# Input.net
KiCad netlist of a schematic drawn in Altium Designer
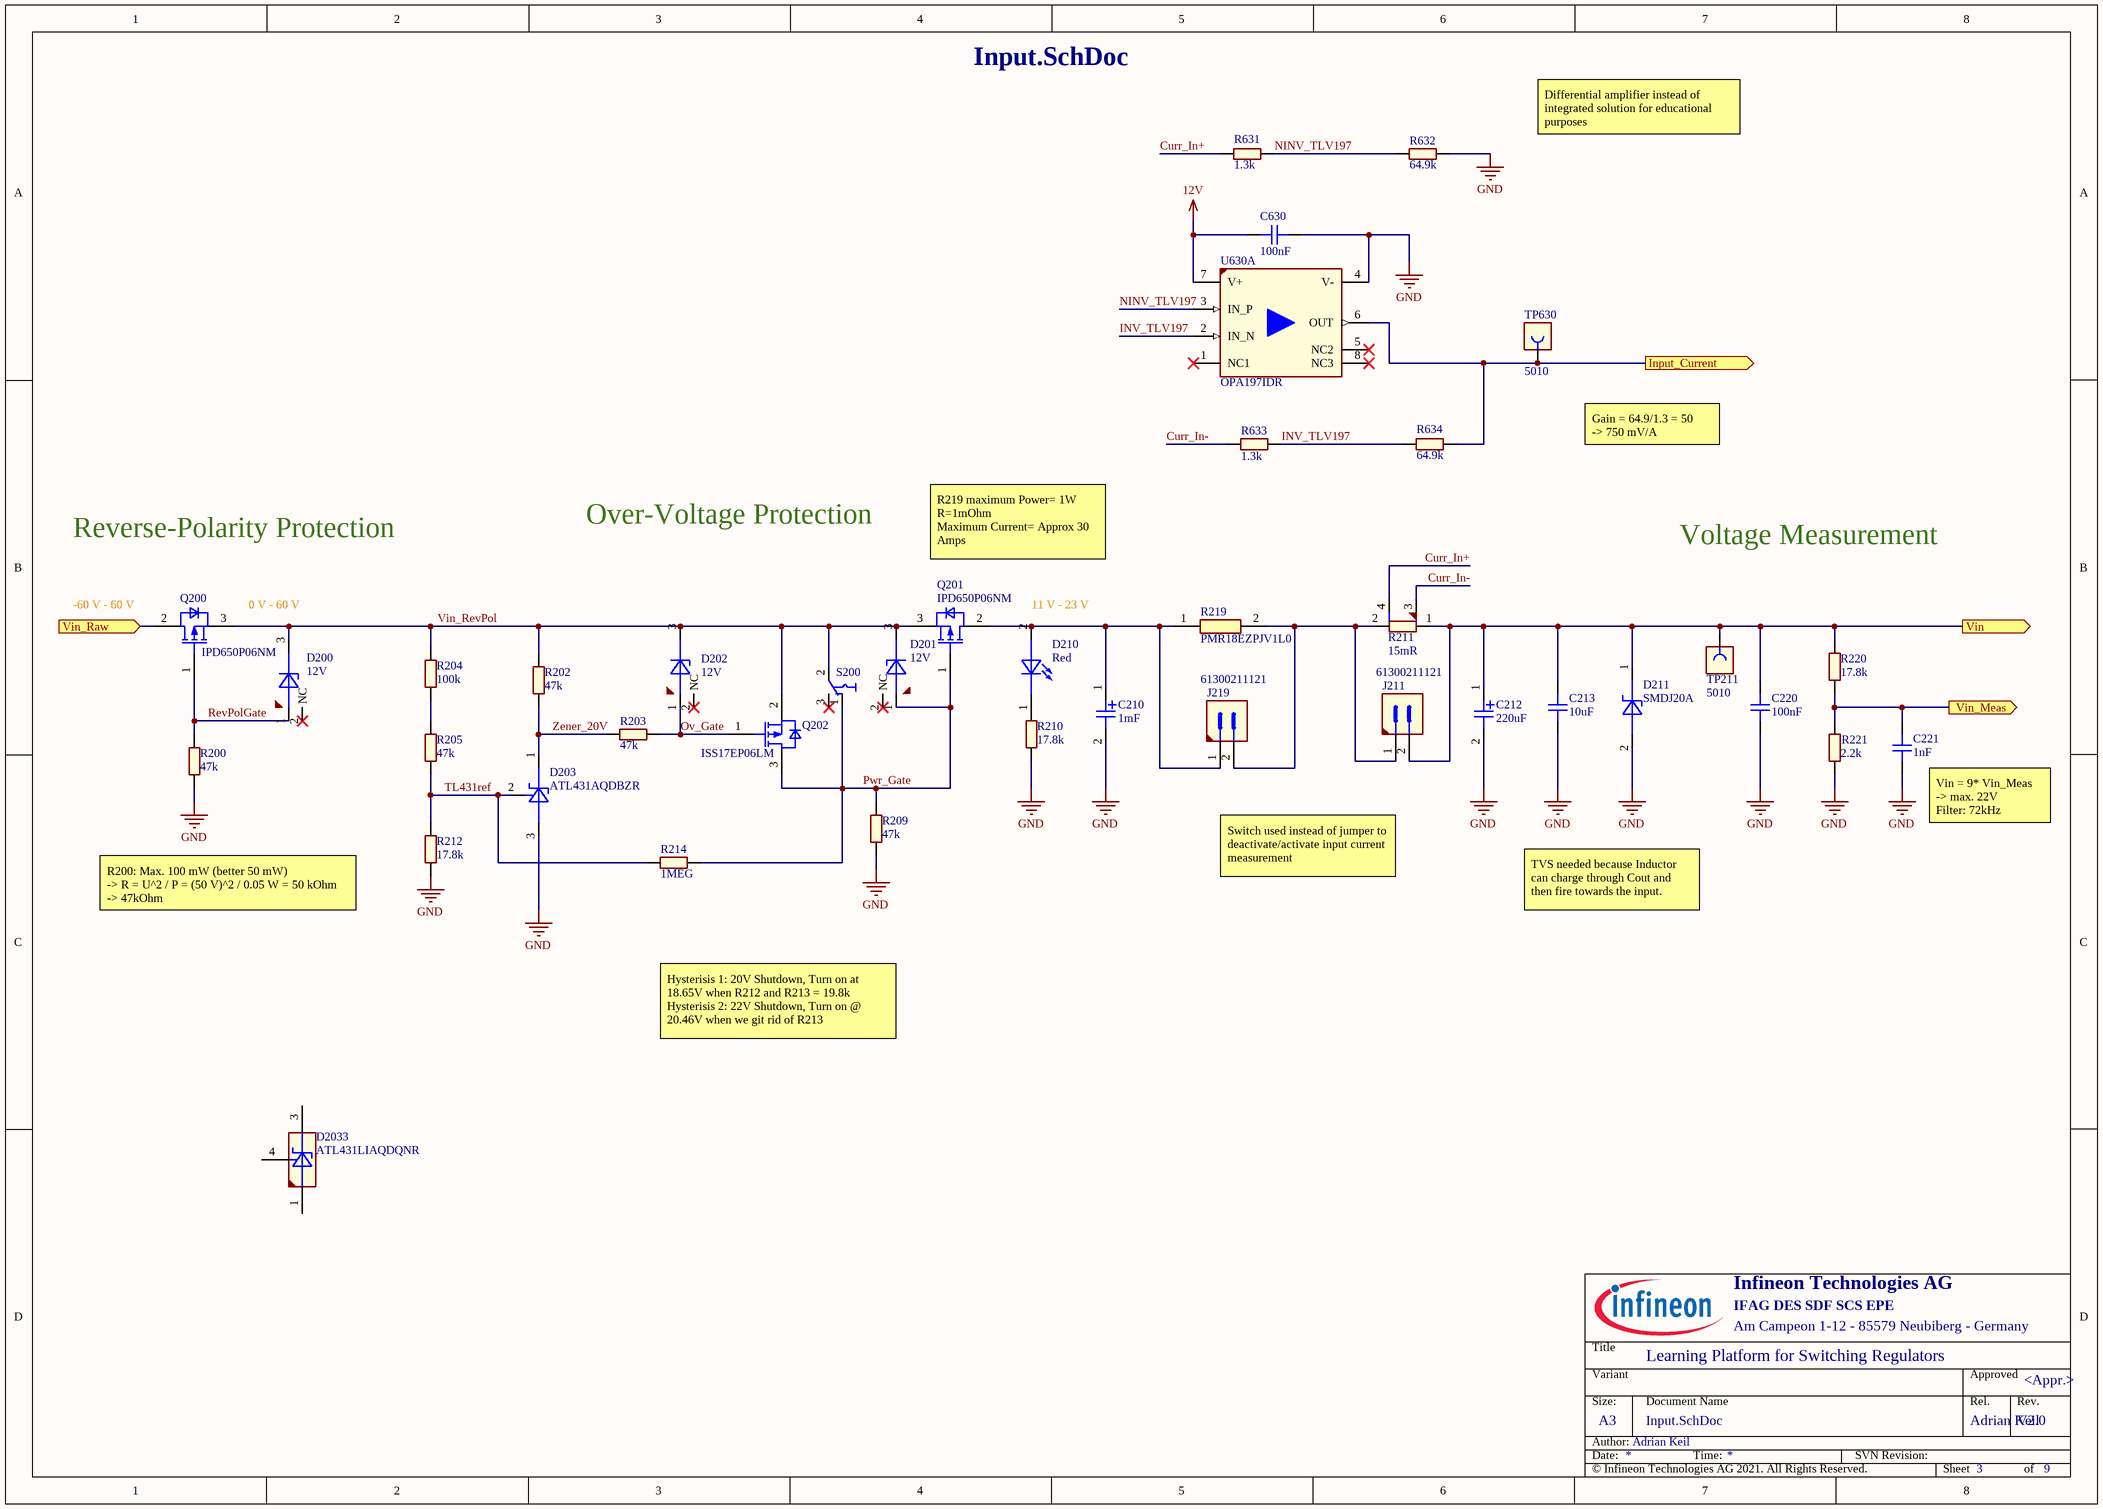
[diagram p0: Input.SchDoc]

(export (version "E")
  (design (tool "Eeschema 10.0.6"))
  (components
    (comp (ref "C210")
      (value "1mF")
      (footprint "CAPPRD500W60D1300H2700B")
      (fields (field (name "MANUFACTURER") "Kemet"))
      (libsource (lib "PCBLibraryData") (part "CAP-SGL-POL-02P_00000002"))
    )
    (comp (ref "C212")
      (value "220uF")
      (footprint "CAPAE1030X1050N-3")
      (fields (field (name "MANUFACTURER") "Nippon Chemi-Con"))
      (libsource (lib "PCBLibraryData") (part "CAP-SGL-POL-02P_00000002"))
    )
    (comp (ref "C213")
      (value "10uF")
      (footprint "CAPC3216X190N-1")
      (description "CAP / CERA / 10uF / 50V / 20% / X5R (EIA) / -55°C to 85°C / 1206 (3216) / SMD / -")
      (fields (field (name "MANUFACTURER") "Taiyo Yuden"))
      (libsource (lib "PCBLibraryData") (part "CAP-SGL-STD-02P_00000001"))
    )
    (comp (ref "C220")
      (value "100nF")
      (footprint "CAPC3216X125N-0")
      (description "CAP / CERA / 100nF / 50V / 10% / X7R (EIA) / -55°C to 125°C / 1206(3216) / SMD / -")
      (fields (field (name "LEGACY PARTNUMBER") "CAP01005660") (field (name "MANUFACTURER") "MuRata"))
      (libsource (lib "PCBLibraryData") (part "CAP-SGL-STD-02P_00000001"))
    )
    (comp (ref "C221")
      (value "1nF")
      (footprint "CAPC3216X95N")
      (description "CAP / CERA / 1nF / 50V / 10% / X7R (EIA) / -55°C to 125°C / 1206(3216) / SMD / -")
      (fields (field (name "LEGACY PARTNUMBER") "CAP01005183") (field (name "MANUFACTURER") "MuRata"))
      (libsource (lib "PCBLibraryData") (part "CAP-SGL-STD-02P_00000001"))
    )
    (comp (ref "C630")
      (value "100nF")
      (footprint "CAPC3216X125N-0")
      (description "CAP / CERA / 100nF / 50V / 10% / X7R (EIA) / -55°C to 125°C / 1206(3216) / SMD / -")
      (fields (field (name "LEGACY PARTNUMBER") "CAP01005660") (field (name "MANUFACTURER") "MuRata"))
      (libsource (lib "PCBLibraryData") (part "CAP-SGL-STD-02P_00000001"))
    )
    (comp (ref "D200")
      (value "12V")
      (footprint "SOT95P230X110-3N")
      (description "Voltage regulator diodes")
      (fields (field (name "MANUFACTURER") "Nexperia"))
      (libsource (lib "PCBLibraryData") (part "d_zener_a1c3_3p"))
    )
    (comp (ref "D201")
      (value "12V")
      (footprint "SOT95P230X110-3N")
      (description "Voltage regulator diodes")
      (fields (field (name "MANUFACTURER") "Nexperia"))
      (libsource (lib "PCBLibraryData") (part "d_zener_a1c3_3p"))
    )
    (comp (ref "D202")
      (value "12V")
      (footprint "SOT95P230X110-3N")
      (description "Voltage regulator diodes")
      (fields (field (name "MANUFACTURER") "Nexperia"))
      (libsource (lib "PCBLibraryData") (part "d_zener_a1c3_3p"))
    )
    (comp (ref "D203")
      (value "ATL431AQDBZR")
      (footprint "SOT95P237X112-3N-1")
      (description "ATL431 Adjustable Precision Shunt Regulator")
      (fields (field (name "MANUFACTURER") "Texas Instruments"))
      (libsource (lib "PCBLibraryData") (part "d_tvs_c1a3_3p"))
    )
    (comp (ref "D210")
      (value "Red")
      (footprint "LEDSC160X80X80-2N-1")
      (description "WL-SMCW SMT Mono-color Chip LED Waterclear, Red,630nm")
      (fields (field (name "MANUFACTURER") "Wurth Elektronik"))
      (libsource (lib "PCBLibraryData") (part "d_led_a"))
    )
    (comp (ref "D211")
      (value "SMDJ20A")
      (footprint "DIOM7959X262N")
      (description "TVS Diode, Low Profile Package, Built in Strain Relief, Glass Passivated Chip Junction")
      (fields (field (name "MANUFACTURER") "Littelfuse"))
      (libsource (lib "PCBLibraryData") (part "d_tvs_a"))
    )
    (comp (ref "D2033")
      (value "ATL431LIAQDQNR")
      (footprint "TI-SMD-X2SON-V")
      (description "High Bandwidth Low-Iq Programmable Shunt Regulator")
      (fields (field (name "MANUFACTURER") "Texas Instruments"))
      (libsource (lib "PCBLibraryData") (part "ATL431LIXXDQNX"))
    )
    (comp (ref "J211")
      (value "61300211121")
      (footprint "CON-M-THT-61300211121")
      (description "Header, 2.54mm Pitch, 2 pin, Vertical, Single Row")
      (fields
        (field (name "LEGACY PARTNUMBER") "CON01500943")
        (field (name "MANUFACTURER") "Wurth Elektronik")
      )
      (libsource (lib "PCBLibraryData") (part "Header 2"))
    )
    (comp (ref "J219")
      (value "61300211121")
      (footprint "CON-M-THT-61300211121")
      (description "Header, 2.54mm Pitch, 2 pin, Vertical, Single Row")
      (fields
        (field (name "LEGACY PARTNUMBER") "CON01500943")
        (field (name "MANUFACTURER") "Wurth Elektronik")
      )
      (libsource (lib "PCBLibraryData") (part "Header 2"))
    )
    (comp (ref "Q200")
      (value "IPD650P06NM")
      (footprint "TO228P998X250-3N-V2")
      (description "OptiMOS Power Transistor, -60 V")
      (fields (field (name "MANUFACTURER") "Infineon Technologies"))
      (libsource (lib "PCBLibraryData") (part "igfet_p_ch_enh_dio_1g2d3s_3p"))
    )
    (comp (ref "Q201")
      (value "IPD650P06NM")
      (footprint "TO228P998X250-3N-V2")
      (description "OptiMOS Power Transistor, -60 V")
      (fields (field (name "MANUFACTURER") "Infineon Technologies"))
      (libsource (lib "PCBLibraryData") (part "igfet_p_ch_enh_dio_1g2d3s_3p"))
    )
    (comp (ref "Q202")
      (value "ISS17EP06LM")
      (footprint "SOT95P240X110-3N-1-V")
      (description "OptiMOSTM Small Signal Transistor, -60 V")
      (fields (field (name "MANUFACTURER") "Infineon Technologies"))
      (libsource (lib "PCBLibraryData") (part "igfet_p_ch_enh_dio_1g2s3d_3p"))
    )
    (comp (ref "R200")
      (value "47k")
      (footprint "RESC3216X60N")
      (description "RES / STD / 47k / 250mW / 1% / 100ppm/K / -55°C to 155°C / 1206(3216) / SMD / -")
      (fields (field (name "LEGACY PARTNUMBER") "RES01802933") (field (name "MANUFACTURER") "Vishay"))
      (libsource (lib "PCBLibraryData") (part "RES-SGL-STD-02P_00000006"))
    )
    (comp (ref "R202")
      (value "47k")
      (footprint "RESC3216X60N")
      (description "RES / STD / 47k / 250mW / 1% / 100ppm/K / -55°C to 155°C / 1206(3216) / SMD / -")
      (fields (field (name "LEGACY PARTNUMBER") "RES01802933") (field (name "MANUFACTURER") "Vishay"))
      (libsource (lib "PCBLibraryData") (part "RES-SGL-STD-02P_00000006"))
    )
    (comp (ref "R203")
      (value "47k")
      (footprint "RESC3216X60N")
      (description "RES / STD / 47k / 250mW / 1% / 100ppm/K / -55°C to 155°C / 1206(3216) / SMD / -")
      (fields (field (name "LEGACY PARTNUMBER") "RES01802933") (field (name "MANUFACTURER") "Vishay"))
      (libsource (lib "") (part "RES-SGL-STD-02P_00000006_2"))
    )
    (comp (ref "R204")
      (value "100k")
      (footprint "RESC3216X60N")
      (description "RES / STD / 100k / 250mW / 1% / 100ppm/K / -55°C to 155°C / 1206(3216) / SMD / -")
      (fields (field (name "LEGACY PARTNUMBER") "RES01802971") (field (name "MANUFACTURER") "Vishay"))
      (libsource (lib "") (part "RES-SGL-STD-02P_00000006_3"))
    )
    (comp (ref "R205")
      (value "47k")
      (footprint "RESC3216X60N")
      (description "RES / STD / 47k / 250mW / 1% / 100ppm/K / -55°C to 155°C / 1206(3216) / SMD / -")
      (fields (field (name "LEGACY PARTNUMBER") "RES01802933") (field (name "MANUFACTURER") "Vishay"))
      (libsource (lib "PCBLibraryData") (part "RES-SGL-STD-02P_00000006"))
    )
    (comp (ref "R209")
      (value "47k")
      (footprint "RESC3216X60N")
      (description "RES / STD / 47k / 250mW / 1% / 100ppm/K / -55°C to 155°C / 1206(3216) / SMD / -")
      (fields (field (name "LEGACY PARTNUMBER") "RES01802933") (field (name "MANUFACTURER") "Vishay"))
      (libsource (lib "PCBLibraryData") (part "RES-SGL-STD-02P_00000006"))
    )
    (comp (ref "R210")
      (value "17.8k")
      (footprint "RESC3216X60N")
      (description "RES / STD / 17.8k / 250mW / 1% / 100ppm/K / -55°C to 155°C / 1206(3216) / SMD / -")
      (fields (field (name "LEGACY PARTNUMBER") "RES01802883") (field (name "MANUFACTURER") "Vishay"))
      (libsource (lib "") (part "RES-SGL-STD-02P_00000006_3"))
    )
    (comp (ref "R211")
      (value "15mR")
      (footprint "RES-SMD-L4T12")
      (description "RES / STD / 15mR / 500mW / 1% / 75ppm/K / -55°C to 155°C / 1206 (3216) / SMD / -")
      (fields (field (name "MANUFACTURER") "Ohmite"))
      (libsource (lib "PCBLibraryData") (part "RES-SHT-STD-04P_00097BE5"))
    )
    (comp (ref "R212")
      (value "17.8k")
      (footprint "RESC3216X60N")
      (description "RES / STD / 17.8k / 250mW / 1% / 100ppm/K / -55°C to 155°C / 1206(3216) / SMD / -")
      (fields (field (name "LEGACY PARTNUMBER") "RES01802883") (field (name "MANUFACTURER") "Vishay"))
      (libsource (lib "") (part "RES-SGL-STD-02P_00000006_3"))
    )
    (comp (ref "R214")
      (value "1MEG")
      (footprint "RESC3216X60N")
      (description "RES / STD / 1MEG / 250mW / 1% / 100ppm/K / -55°C to 155°C / 1206(3216) / SMD / -")
      (fields (field (name "LEGACY PARTNUMBER") "RES01803085") (field (name "MANUFACTURER") "Vishay"))
      (libsource (lib "") (part "RES-SGL-STD-02P_00000006_1"))
    )
    (comp (ref "R219")
      (value "PMR18EZPJV1L0")
      (footprint "SamacSys:RESC3216X59N")
      (description "Resistor")
      (fields (field (name "MOUSER PART NUMBER") "755-PMR18EZPJV1L0"))
      (libsource (lib "*") (part "PMR18EZPJV1L0"))
    )
    (comp (ref "R220")
      (value "17.8k")
      (footprint "RESC3216X60N")
      (description "RES / STD / 17.8k / 250mW / 1% / 100ppm/K / -55°C to 155°C / 1206(3216) / SMD / -")
      (fields (field (name "LEGACY PARTNUMBER") "RES01802883") (field (name "MANUFACTURER") "Vishay"))
      (libsource (lib "") (part "RES-SGL-STD-02P_00000006_3"))
    )
    (comp (ref "R221")
      (value "2.2k")
      (footprint "RESC3216X60N")
      (description "RES / STD / 2.2k / 250mW / 1% / 100ppm/K / -55°C to 155°C / 1206(3216) / SMD / -")
      (fields (field (name "LEGACY PARTNUMBER") "RES01802779") (field (name "MANUFACTURER") "Vishay"))
      (libsource (lib "") (part "RES-SGL-STD-02P_00000006_3"))
    )
    (comp (ref "R631")
      (value "1.3k")
      (footprint "RESC3216X60N")
      (description "RES / STD / 1.3k / 250mW / 1% / 100ppm/K / -55°C to 155°C / 1206(3216) / SMD / -")
      (fields (field (name "LEGACY PARTNUMBER") "RES01802755") (field (name "MANUFACTURER") "Vishay"))
      (libsource (lib "") (part "RES-SGL-STD-02P_00000006_1"))
    )
    (comp (ref "R632")
      (value "64.9k")
      (footprint "RESC3216X60N")
      (description "RES / STD / 64.9k / 250mW / 1% / 100ppm/K / -55°C to 155°C / 1206(3216) / SMD / -")
      (fields (field (name "LEGACY PARTNUMBER") "RES01802950") (field (name "MANUFACTURER") "Vishay"))
      (libsource (lib "") (part "RES-SGL-STD-02P_00000006_1"))
    )
    (comp (ref "R633")
      (value "1.3k")
      (footprint "RESC3216X60N")
      (description "RES / STD / 1.3k / 250mW / 1% / 100ppm/K / -55°C to 155°C / 1206(3216) / SMD / -")
      (fields (field (name "LEGACY PARTNUMBER") "RES01802755") (field (name "MANUFACTURER") "Vishay"))
      (libsource (lib "") (part "RES-SGL-STD-02P_00000006_1"))
    )
    (comp (ref "R634")
      (value "64.9k")
      (footprint "RESC3216X60N")
      (description "RES / STD / 64.9k / 250mW / 1% / 100ppm/K / -55°C to 155°C / 1206(3216) / SMD / -")
      (fields (field (name "LEGACY PARTNUMBER") "RES01802950") (field (name "MANUFACTURER") "Vishay"))
      (libsource (lib "") (part "RES-SGL-STD-02P_00000006_1"))
    )
    (comp (ref "S200")
      (value "CL-SB-12A-01T")
      (footprint "SW-SMD-CL-SB-12A-01T")
      (description "Slid Switch, 12V, 200mA")
      (fields (field (name "MANUFACTURER") "NIDEC COPAL ELECTRONICS, Inc."))
      (libsource (lib "PCBLibraryData") (part "sw_co213_3p"))
    )
    (comp (ref "TP211")
      (value "5010")
      (footprint "CON-THT-TP-5010")
      (description "PC Test Point-Multipurpose THT, Red")
      (fields
        (field (name "LEGACY PARTNUMBER") "CON01500529")
        (field (name "MANUFACTURER") "Keystone Electronics Corp.")
      )
      (libsource (lib "") (part "connector_1_f_1"))
    )
    (comp (ref "TP630")
      (value "5010")
      (footprint "CON-THT-TP-5010")
      (description "PC Test Point-Multipurpose THT, Red")
      (fields
        (field (name "LEGACY PARTNUMBER") "CON01500529")
        (field (name "MANUFACTURER") "Keystone Electronics Corp.")
      )
      (libsource (lib "PCBLibraryData") (part "connector_1_f"))
    )
    (comp (ref "U630")
      (value "OPA197IDR")
      (footprint "SOIC127P600X175-8N-23")
      (fields (field (name "MANUFACTURER") "Texas Instruments"))
      (libsource (lib "PCBLibraryData") (part "OPA140AID"))
    )
  )
  (nets
    (net (code "1") (name "/Curr_In+") (class "Default")
      (node (ref "R211") (pin "4") (pinfunction "I2_4") (pintype "passive"))
      (node (ref "R631") (pin "1") (pinfunction "1_1") (pintype "passive"))
    )
    (net (code "2") (name "/Curr_In-") (class "Default")
      (node (ref "R211") (pin "3") (pinfunction "I1_3") (pintype "passive"))
      (node (ref "R633") (pin "1") (pinfunction "1_1") (pintype "passive"))
    )
    (net (code "3") (name "/INV_TLV197") (class "Default")
      (node (ref "R633") (pin "2") (pinfunction "2_2") (pintype "passive"))
      (node (ref "R634") (pin "1") (pinfunction "1_1") (pintype "passive"))
      (node (ref "U630") (pin "2") (pinfunction "IN_N_2") (pintype "input"))
    )
    (net (code "4") (name "/Input_Current") (class "Default")
      (node (ref "R634") (pin "2") (pinfunction "2_2") (pintype "passive"))
      (node (ref "TP630") (pin "1") (pinfunction "1_1") (pintype "passive"))
      (node (ref "U630") (pin "6") (pinfunction "OUT_6") (pintype "output"))
    )
    (net (code "5") (name "/NINV_TLV197") (class "Default")
      (node (ref "R631") (pin "2") (pinfunction "2_2") (pintype "passive"))
      (node (ref "R632") (pin "1") (pinfunction "1_1") (pintype "passive"))
      (node (ref "U630") (pin "3") (pinfunction "IN_P_3") (pintype "input"))
    )
    (net (code "6") (name "/Ov_Gate") (class "Default")
      (node (ref "D202") (pin "1") (pinfunction "ANODE_1") (pintype "passive"))
      (node (ref "Q202") (pin "1") (pinfunction "GATE_1") (pintype "passive"))
      (node (ref "R203") (pin "1") (pinfunction "1_1") (pintype "passive"))
    )
    (net (code "7") (name "/Pwr_Gate") (class "Default")
      (node (ref "D201") (pin "1") (pinfunction "ANODE_1") (pintype "passive"))
      (node (ref "Q201") (pin "1") (pinfunction "GATE_1") (pintype "passive"))
      (node (ref "Q202") (pin "3") (pinfunction "DRAIN_3") (pintype "passive"))
      (node (ref "R209") (pin "2") (pinfunction "2_2") (pintype "passive"))
      (node (ref "R214") (pin "2") (pinfunction "2_2") (pintype "passive"))
      (node (ref "S200") (pin "1") (pinfunction "1_1") (pintype "passive"))
    )
    (net (code "8") (name "/RevPolGate") (class "Default")
      (node (ref "D200") (pin "1") (pinfunction "ANODE_1") (pintype "passive"))
      (node (ref "Q200") (pin "1") (pinfunction "GATE_1") (pintype "passive"))
      (node (ref "R200") (pin "2") (pinfunction "2_2") (pintype "passive"))
    )
    (net (code "9") (name "/TL431ref") (class "Default")
      (node (ref "D203") (pin "2") (pinfunction "REF_2") (pintype "passive"))
      (node (ref "R205") (pin "1") (pinfunction "1_1") (pintype "passive"))
      (node (ref "R212") (pin "1") (pinfunction "1_1") (pintype "passive"))
      (node (ref "R214") (pin "1") (pinfunction "1_1") (pintype "passive"))
    )
    (net (code "10") (name "/Vin") (class "Default")
      (node (ref "C212") (pin "1") (pinfunction "1_1") (pintype "passive"))
      (node (ref "C213") (pin "2") (pinfunction "2_2") (pintype "passive"))
      (node (ref "C220") (pin "1") (pinfunction "1_1") (pintype "passive"))
      (node (ref "D211") (pin "1") (pinfunction "CATHODE_1") (pintype "passive"))
      (node (ref "J211") (pin "2") (pinfunction "2_2") (pintype "passive"))
      (node (ref "R211") (pin "1") (pinfunction "V1_1") (pintype "passive"))
      (node (ref "R220") (pin "1") (pinfunction "1_1") (pintype "passive"))
      (node (ref "TP211") (pin "1") (pinfunction "1_1") (pintype "passive"))
    )
    (net (code "11") (name "/Vin_Meas") (class "Default")
      (node (ref "C221") (pin "2") (pinfunction "2_2") (pintype "passive"))
      (node (ref "R220") (pin "2") (pinfunction "2_2") (pintype "passive"))
      (node (ref "R221") (pin "1") (pinfunction "1_1") (pintype "passive"))
    )
    (net (code "12") (name "/Vin_Raw") (class "Default")
      (node (ref "Q200") (pin "2") (pinfunction "DRAIN_2") (pintype "passive"))
    )
    (net (code "13") (name "/Vin_RevPol") (class "Default")
      (node (ref "D200") (pin "3") (pinfunction "CATHODE_3") (pintype "passive"))
      (node (ref "D201") (pin "3") (pinfunction "CATHODE_3") (pintype "passive"))
      (node (ref "D202") (pin "3") (pinfunction "CATHODE_3") (pintype "passive"))
      (node (ref "Q200") (pin "3") (pinfunction "SOURCE_3") (pintype "passive"))
      (node (ref "Q201") (pin "3") (pinfunction "SOURCE_3") (pintype "passive"))
      (node (ref "Q202") (pin "2") (pinfunction "SOURCE_2") (pintype "passive"))
      (node (ref "R202") (pin "2") (pinfunction "2_2") (pintype "passive"))
      (node (ref "R204") (pin "1") (pinfunction "1_1") (pintype "passive"))
      (node (ref "S200") (pin "2") (pinfunction "2_2") (pintype "passive"))
    )
    (net (code "14") (name "/Zener_20V") (class "Default")
      (node (ref "D203") (pin "1") (pinfunction "CATHODE_1") (pintype "passive"))
      (node (ref "R202") (pin "1") (pinfunction "1_1") (pintype "passive"))
      (node (ref "R203") (pin "2") (pinfunction "2_2") (pintype "passive"))
    )
    (net (code "15") (name "12V") (class "Default")
      (node (ref "C630") (pin "2") (pinfunction "2_2") (pintype "passive"))
      (node (ref "U630") (pin "7") (pinfunction "V+_7") (pintype "power_in"))
    )
    (net (code "16") (name "EP") (class "Default")
      (node (ref "D2033") (pin "5") (pinfunction "EP_5") (pintype "power_in"))
    )
    (net (code "17") (name "GND") (class "Default")
      (node (ref "C210") (pin "2") (pinfunction "2_2") (pintype "passive"))
      (node (ref "C212") (pin "2") (pinfunction "2_2") (pintype "passive"))
      (node (ref "C213") (pin "1") (pinfunction "1_1") (pintype "passive"))
      (node (ref "C220") (pin "2") (pinfunction "2_2") (pintype "passive"))
      (node (ref "C221") (pin "1") (pinfunction "1_1") (pintype "passive"))
      (node (ref "C630") (pin "1") (pinfunction "1_1") (pintype "passive"))
      (node (ref "D203") (pin "3") (pinfunction "ANODE_3") (pintype "passive"))
      (node (ref "D211") (pin "2") (pinfunction "ANODE_2") (pintype "passive"))
      (node (ref "R200") (pin "1") (pinfunction "1_1") (pintype "passive"))
      (node (ref "R209") (pin "1") (pinfunction "1_1") (pintype "passive"))
      (node (ref "R210") (pin "2") (pinfunction "2_2") (pintype "passive"))
      (node (ref "R212") (pin "2") (pinfunction "2_2") (pintype "passive"))
      (node (ref "R221") (pin "2") (pinfunction "2_2") (pintype "passive"))
      (node (ref "R632") (pin "2") (pinfunction "2_2") (pintype "passive"))
      (node (ref "U630") (pin "4") (pinfunction "V-_4") (pintype "power_in"))
    )
    (net (code "18") (name "Net-(D210-Anode)") (class "Default")
      (node (ref "C210") (pin "1") (pinfunction "1_1") (pintype "passive"))
      (node (ref "D210") (pin "2") (pinfunction "Anode_2") (pintype "passive"))
      (node (ref "J219") (pin "1") (pinfunction "1_1") (pintype "passive"))
      (node (ref "Q201") (pin "2") (pinfunction "DRAIN_2") (pintype "passive"))
      (node (ref "R219") (pin "1") (pinfunction "1_1") (pintype "passive"))
    )
    (net (code "19") (name "Net-(D210-Cathode)") (class "Default")
      (node (ref "D210") (pin "1") (pinfunction "Cathode_1") (pintype "passive"))
      (node (ref "R210") (pin "1") (pinfunction "1_1") (pintype "passive"))
    )
    (net (code "20") (name "Net-(R204-Pad2)") (class "Default")
      (node (ref "R204") (pin "2") (pinfunction "2_2") (pintype "passive"))
      (node (ref "R205") (pin "2") (pinfunction "2_2") (pintype "passive"))
    )
    (net (code "21") (name "Net-(R211-V2)") (class "Default")
      (node (ref "J211") (pin "1") (pinfunction "1_1") (pintype "passive"))
      (node (ref "J219") (pin "2") (pinfunction "2_2") (pintype "passive"))
      (node (ref "R211") (pin "2") (pinfunction "V2_2") (pintype "passive"))
      (node (ref "R219") (pin "2") (pinfunction "2_2") (pintype "passive"))
    )
    (net (code "22") (name "unconnected-(D200-NC-Pad2)") (class "Default")
      (node (ref "D200") (pin "2") (pinfunction "NC_2") (pintype "passive+no_connect"))
    )
    (net (code "23") (name "unconnected-(D201-NC-Pad2)") (class "Default")
      (node (ref "D201") (pin "2") (pinfunction "NC_2") (pintype "passive+no_connect"))
    )
    (net (code "24") (name "unconnected-(D202-NC-Pad2)") (class "Default")
      (node (ref "D202") (pin "2") (pinfunction "NC_2") (pintype "passive+no_connect"))
    )
    (net (code "25") (name "unconnected-(D2033-A-Pad1)") (class "Default")
      (node (ref "D2033") (pin "1") (pinfunction "A_1") (pintype "passive"))
    )
    (net (code "26") (name "unconnected-(D2033-C-Pad3)") (class "Default")
      (node (ref "D2033") (pin "3") (pinfunction "C_3") (pintype "passive"))
    )
    (net (code "27") (name "unconnected-(D2033-NC-Pad2)") (class "Default")
      (node (ref "D2033") (pin "2") (pinfunction "NC_2") (pintype "passive"))
    )
    (net (code "28") (name "unconnected-(D2033-REF-Pad4)") (class "Default")
      (node (ref "D2033") (pin "4") (pinfunction "REF_4") (pintype "passive"))
    )
    (net (code "29") (name "unconnected-(S200-Pad3)") (class "Default")
      (node (ref "S200") (pin "3") (pinfunction "3_3") (pintype "passive+no_connect"))
    )
    (net (code "30") (name "unconnected-(U630-NC1-Pad1)") (class "Default")
      (node (ref "U630") (pin "1") (pinfunction "NC1_1") (pintype "passive+no_connect"))
    )
    (net (code "31") (name "unconnected-(U630-NC2-Pad5)") (class "Default")
      (node (ref "U630") (pin "5") (pinfunction "NC2_5") (pintype "passive+no_connect"))
    )
    (net (code "32") (name "unconnected-(U630-NC3-Pad8)") (class "Default")
      (node (ref "U630") (pin "8") (pinfunction "NC3_8") (pintype "passive+no_connect"))
    )
  )
)
